# Senslope_Alpha_5_0.net
KiCad netlist of a schematic drawn in EAGLE
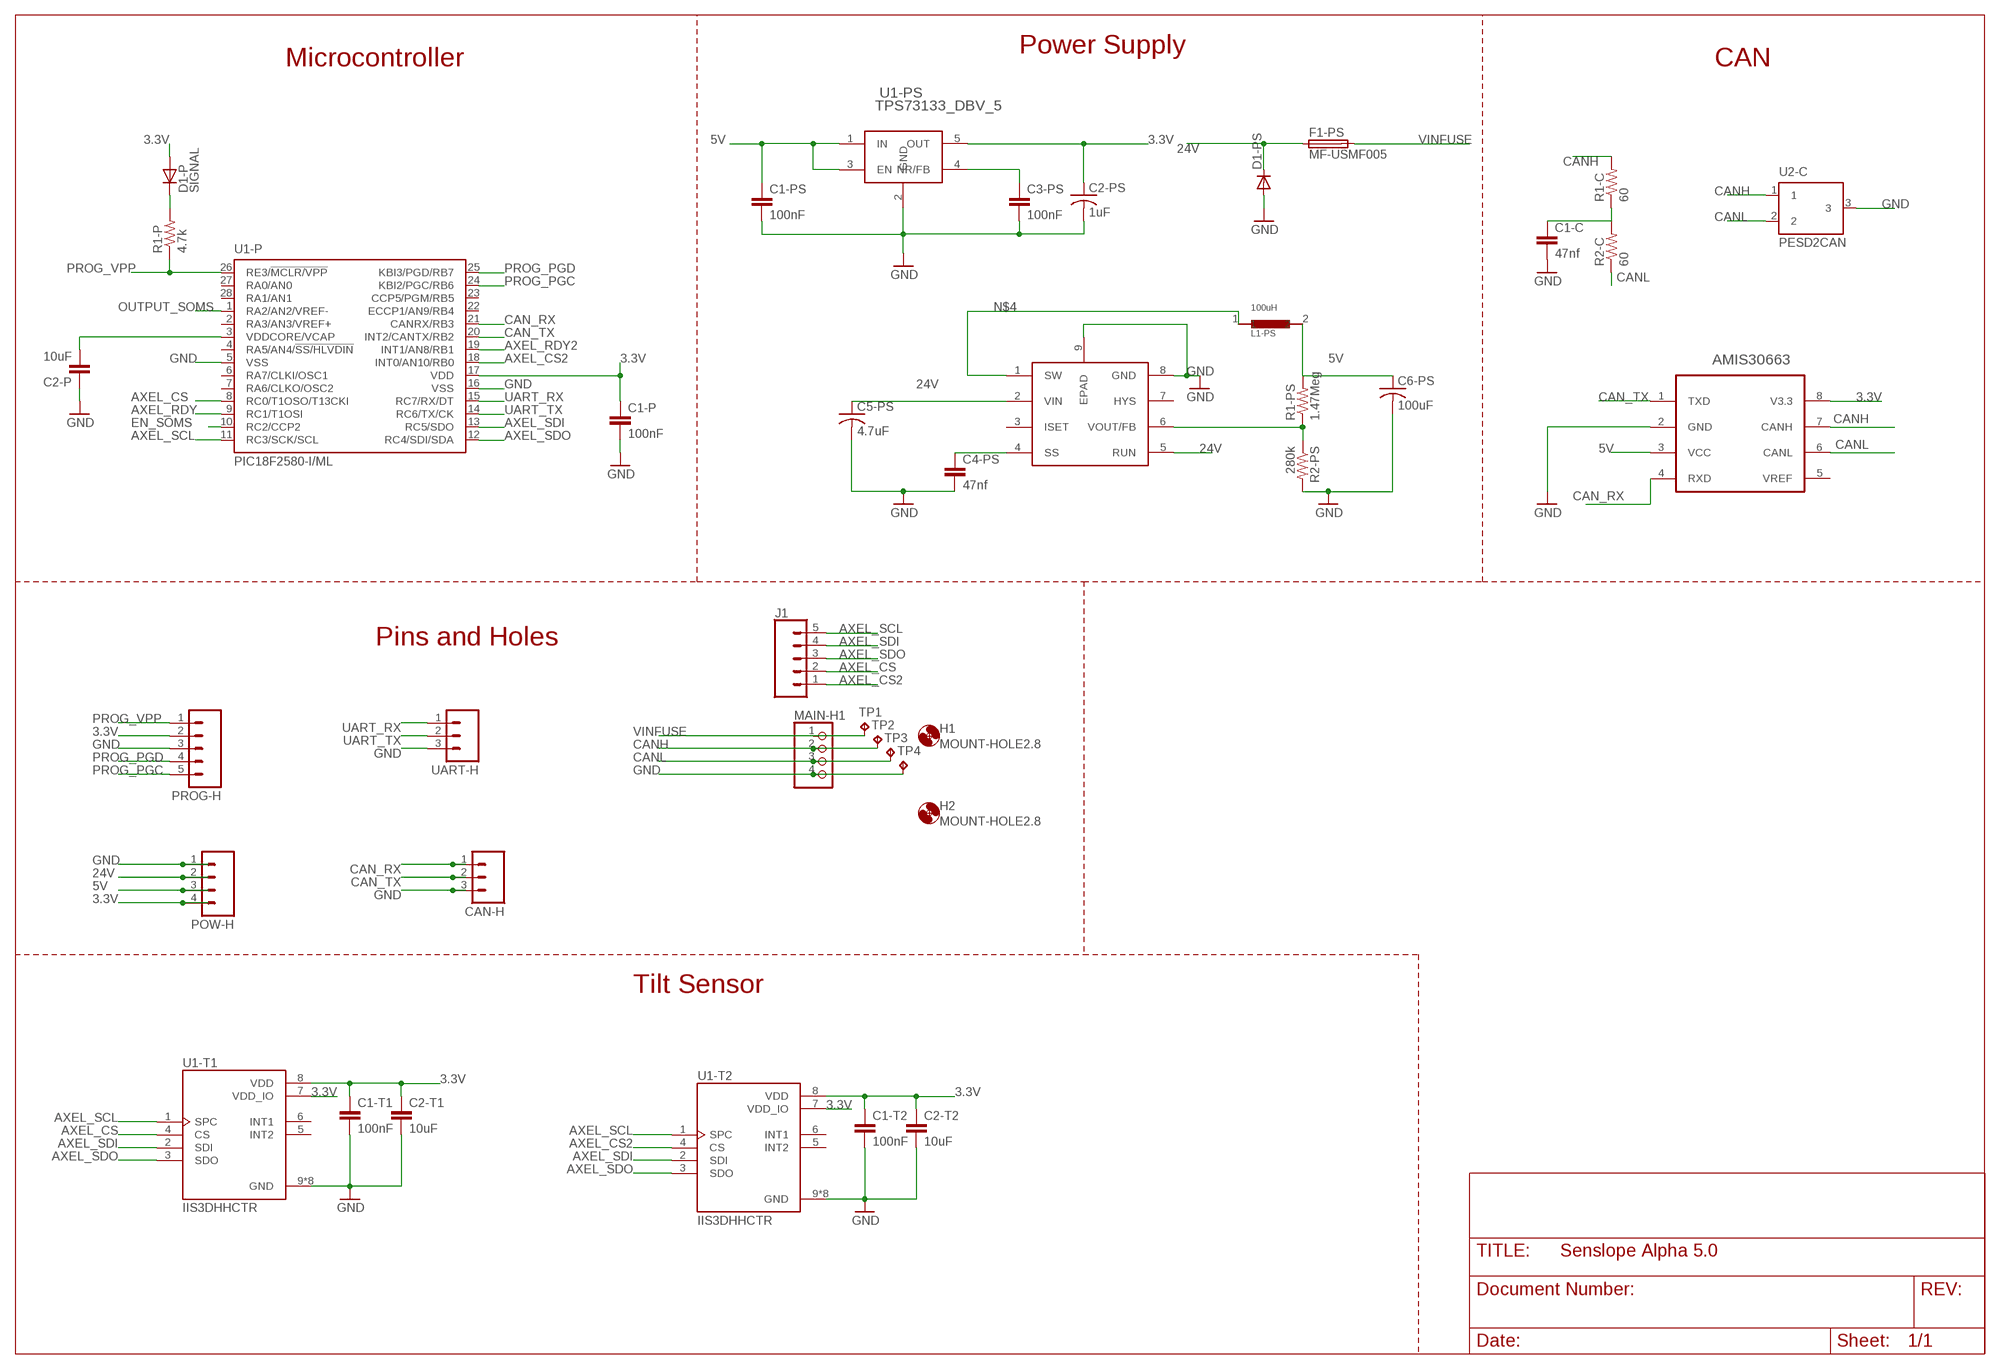
[diagram p0: schematic, sheet 1]

(export (version "E")
  (design (tool "Eeschema 10.0.6"))
  (components
    (comp (ref "C1-C")
      (value "47nf")
      (footprint "eagle-import:C0805")
      (libsource (lib "eagle-import") (part "C-EUC0805"))
    )
    (comp (ref "C1-P")
      (value "100nF")
      (footprint "eagle-import:C0603")
      (libsource (lib "eagle-import") (part "resistor_C-EUC0603"))
    )
    (comp (ref "C1-PS")
      (value "100nF")
      (footprint "eagle-import:C0603")
      (libsource (lib "eagle-import") (part "C-EUC0603"))
    )
    (comp (ref "C1-T1")
      (value "100nF")
      (footprint "eagle-import:C0603")
      (libsource (lib "eagle-import") (part "C-EUC0603"))
    )
    (comp (ref "C1-T2")
      (value "100nF")
      (footprint "eagle-import:C0603")
      (libsource (lib "eagle-import") (part "C-EUC0603"))
    )
    (comp (ref "C2-P")
      (value "10uF")
      (footprint "eagle-import:C0603")
      (libsource (lib "eagle-import") (part "C-EUC0603"))
    )
    (comp (ref "C2-PS")
      (value "1uF")
      (footprint "eagle-import:C0402")
      (libsource (lib "eagle-import") (part "C-USC0402"))
    )
    (comp (ref "C2-T1")
      (value "10uF")
      (footprint "eagle-import:C0603")
      (libsource (lib "eagle-import") (part "C-EUC0603"))
    )
    (comp (ref "C2-T2")
      (value "10uF")
      (footprint "eagle-import:C0603")
      (libsource (lib "eagle-import") (part "C-EUC0603"))
    )
    (comp (ref "C3-PS")
      (value "100nF")
      (footprint "eagle-import:C0603")
      (libsource (lib "eagle-import") (part "C-EUC0603"))
    )
    (comp (ref "C4-PS")
      (value "47nf")
      (footprint "eagle-import:C0805")
      (libsource (lib "eagle-import") (part "C-EUC0805"))
    )
    (comp (ref "C5-PS")
      (value "4.7uF")
      (footprint "eagle-import:C1206K")
      (libsource (lib "eagle-import") (part "C-USC1206K"))
    )
    (comp (ref "C6-PS")
      (value "100uF")
      (footprint "eagle-import:C1210K")
      (libsource (lib "eagle-import") (part "C-USC1210K"))
    )
    (comp (ref "CAN-H")
      (value "UART")
      (footprint "eagle-import:1X03_NO_SILK")
      (libsource (lib "eagle-import") (part "M031X03_NO_SILK"))
    )
    (comp (ref "D1-P")
      (value "SIGNAL")
      (footprint "eagle-import:DIODE-0603")
      (libsource (lib "eagle-import") (part "DIODE0603"))
    )
    (comp (ref "D1-PS")
      (value "DIODE-DO-214AC")
      (footprint "eagle-import:DO-214AC")
      (libsource (lib "eagle-import") (part "DIODE-DO-214AC"))
    )
    (comp (ref "F1-PS")
      (value "MF-USMF005")
      (footprint "eagle-import:1210")
      (libsource (lib "eagle-import") (part "MF-USMF075"))
    )
    (comp (ref "H1")
      (value "MOUNT-HOLE2.8")
      (footprint "eagle-import:2,8")
      (libsource (lib "eagle-import") (part "MOUNT-HOLE2.8"))
    )
    (comp (ref "H2")
      (value "MOUNT-HOLE2.8")
      (footprint "eagle-import:2,8")
      (libsource (lib "eagle-import") (part "MOUNT-HOLE2.8"))
    )
    (comp (ref "J1")
      (value "CONN_05NO_SILK")
      (footprint "eagle-import:1X05_NO_SILK")
      (libsource (lib "eagle-import") (part "CONN_05NO_SILK"))
    )
    (comp (ref "L1-PS")
      (value "100uH")
      (footprint "eagle-import:1210")
      (libsource (lib "eagle-import") (part "LQH32PN101MN0L"))
    )
    (comp (ref "MAIN-H1")
      (value "PINHD-1X04_2.54")
      (footprint "eagle-import:1X04")
      (libsource (lib "eagle-import") (part "PINHD-1X04_2.54"))
    )
    (comp (ref "POW-H")
      (value "M041X04_NO_SILK")
      (footprint "eagle-import:1X04_NO_SILK")
      (libsource (lib "eagle-import") (part "M041X04_NO_SILK"))
    )
    (comp (ref "PROG-H")
      (value "M05PTH")
      (footprint "eagle-import:1X05@1")
      (libsource (lib "eagle-import") (part "M05PTH"))
    )
    (comp (ref "R1-C")
      (value "60")
      (footprint "eagle-import:R0805")
      (libsource (lib "eagle-import") (part "R-US_R0805"))
    )
    (comp (ref "R1-P")
      (value "4.7k")
      (footprint "eagle-import:R0603")
      (libsource (lib "eagle-import") (part "resistor_R-US_R0603"))
    )
    (comp (ref "R1-PS")
      (value "1.47Meg")
      (footprint "eagle-import:R0805")
      (libsource (lib "eagle-import") (part "R-US_R0805"))
    )
    (comp (ref "R2-C")
      (value "60")
      (footprint "eagle-import:R0805")
      (libsource (lib "eagle-import") (part "R-US_R0805"))
    )
    (comp (ref "R2-PS")
      (value "280k")
      (footprint "eagle-import:R0805")
      (libsource (lib "eagle-import") (part "R-US_R0805"))
    )
    (comp (ref "TP1")
      (value "TPTP10SQ")
      (footprint "eagle-import:TP10SQ")
      (libsource (lib "eagle-import") (part "TPTP10SQ"))
    )
    (comp (ref "TP2")
      (value "TPTP10SQ")
      (footprint "eagle-import:TP10SQ")
      (libsource (lib "eagle-import") (part "TPTP10SQ"))
    )
    (comp (ref "TP3")
      (value "TPTP10SQ")
      (footprint "eagle-import:TP10SQ")
      (libsource (lib "eagle-import") (part "TPTP10SQ"))
    )
    (comp (ref "TP4")
      (value "TPTP10SQ")
      (footprint "eagle-import:TP10SQ")
      (libsource (lib "eagle-import") (part "TPTP10SQ"))
    )
    (comp (ref "U1-P")
      (value "PIC18F2580-I/ML")
      (footprint "eagle-import:QFN28-ML_6X6MM")
      (fields (field (name "MF") "MICROCHIP"))
      (libsource (lib "eagle-import") (part "PIC18F280-I/ML5"))
    )
    (comp (ref "U1-PS")
      (value "TPS73133_DBV_5")
      (footprint "eagle-import:DBV5")
      (fields
        (field (name "GENERIC_PART_NUMBER") "TPS73133")
        (field (name "MANUFACTURER") "Texas Instruments")
        (field (name "MANUFACTURER_PART_NUMBER") "tps73133_dbv_5")
      )
      (libsource (lib "eagle-import") (part "TPS73133_DBV_5"))
    )
    (comp (ref "U1-T1")
      (value "IIS3DHHCTR")
      (footprint "eagle-import:IC_IIS3DHHCTR")
      (fields (field (name "MF") "STMicroelectronics"))
      (libsource (lib "eagle-import") (part "IIS3DHHCTR"))
    )
    (comp (ref "U1-T2")
      (value "IIS3DHHCTR")
      (footprint "eagle-import:IC_IIS3DHHCTR")
      (fields (field (name "MF") "STMicroelectronics"))
      (libsource (lib "eagle-import") (part "IIS3DHHCTR"))
    )
    (comp (ref "U2")
      (value "AMIS30663CAN")
      (footprint "eagle-import:SOIC8")
      (fields (field (name "MPN") "AMIS30663"))
      (libsource (lib "eagle-import") (part "AMIS30663CAN"))
    )
    (comp (ref "U2-C")
      (value "PESD2CAN")
      (footprint "eagle-import:SOT23")
      (libsource (lib "eagle-import") (part "PESD2CAN"))
    )
    (comp (ref "U2-PS")
      (value "LTC3631-5")
      (footprint "eagle-import:MSOP8E")
      (libsource (lib "eagle-import") (part "LTC3631"))
    )
    (comp (ref "UART-H")
      (value "UART")
      (footprint "eagle-import:1X03_NO_SILK")
      (libsource (lib "eagle-import") (part "M031X03_NO_SILK"))
    )
  )
  (nets
    (net (code "1") (name "/3.3V") (class "Default")
      (node (ref "C1-P") (pin "1") (pinfunction "1_1") (pintype "passive"))
      (node (ref "C1-T1") (pin "1") (pinfunction "1_1") (pintype "passive"))
      (node (ref "C1-T2") (pin "1") (pinfunction "1_1") (pintype "passive"))
      (node (ref "C2-PS") (pin "1") (pinfunction "1_1") (pintype "passive"))
      (node (ref "C2-T1") (pin "1") (pinfunction "1_1") (pintype "passive"))
      (node (ref "C2-T2") (pin "1") (pinfunction "1_1") (pintype "passive"))
      (node (ref "D1-P") (pin "A") (pinfunction "A_A") (pintype "passive"))
      (node (ref "POW-H") (pin "4") (pinfunction "4_4") (pintype "passive"))
      (node (ref "PROG-H") (pin "2") (pinfunction "2_2") (pintype "passive"))
      (node (ref "U1-P") (pin "17") (pinfunction "VDD_17") (pintype "power_in"))
      (node (ref "U1-PS") (pin "5") (pinfunction "OUT_5") (pintype "output"))
      (node (ref "U1-T1") (pin "7") (pinfunction "VDD_IO_7") (pintype "power_in"))
      (node (ref "U1-T1") (pin "8") (pinfunction "VDD_8") (pintype "power_in"))
      (node (ref "U1-T2") (pin "7") (pinfunction "VDD_IO_7") (pintype "power_in"))
      (node (ref "U1-T2") (pin "8") (pinfunction "VDD_8") (pintype "power_in"))
      (node (ref "U2") (pin "8") (pinfunction "V3.3_8") (pintype "bidirectional"))
    )
    (net (code "2") (name "/5V") (class "Default")
      (node (ref "C1-PS") (pin "1") (pinfunction "1_1") (pintype "passive"))
      (node (ref "C6-PS") (pin "1") (pinfunction "1_1") (pintype "passive"))
      (node (ref "L1-PS") (pin "2") (pinfunction "2_2") (pintype "bidirectional"))
      (node (ref "POW-H") (pin "3") (pinfunction "3_3") (pintype "passive"))
      (node (ref "R1-PS") (pin "2") (pinfunction "2_2") (pintype "passive"))
      (node (ref "U1-PS") (pin "1") (pinfunction "IN_1") (pintype "input"))
      (node (ref "U1-PS") (pin "3") (pinfunction "EN_3") (pintype "passive"))
      (node (ref "U2") (pin "3") (pinfunction "VCC_3") (pintype "bidirectional"))
    )
    (net (code "3") (name "/24V") (class "Default")
      (node (ref "C5-PS") (pin "1") (pinfunction "1_1") (pintype "passive"))
      (node (ref "D1-PS") (pin "1") (pinfunction "C_1") (pintype "passive"))
      (node (ref "F1-PS") (pin "1") (pinfunction "1_1") (pintype "passive"))
      (node (ref "POW-H") (pin "2") (pinfunction "2_2") (pintype "passive"))
      (node (ref "U2-PS") (pin "2") (pinfunction "VIN_2") (pintype "bidirectional"))
      (node (ref "U2-PS") (pin "5") (pinfunction "RUN_5") (pintype "bidirectional"))
    )
    (net (code "4") (name "/AXEL_CS") (class "Default")
      (node (ref "J1") (pin "2") (pinfunction "2_2") (pintype "passive"))
      (node (ref "U1-P") (pin "8") (pinfunction "RC0/T1OSO/T13CKI_8") (pintype "bidirectional"))
      (node (ref "U1-T1") (pin "4") (pinfunction "CS_4") (pintype "input"))
    )
    (net (code "5") (name "/AXEL_CS2") (class "Default")
      (node (ref "J1") (pin "1") (pinfunction "1_1") (pintype "passive"))
      (node (ref "U1-P") (pin "18") (pinfunction "INT0/AN10/RB0_18") (pintype "bidirectional"))
      (node (ref "U1-T2") (pin "4") (pinfunction "CS_4") (pintype "input"))
    )
    (net (code "6") (name "/AXEL_RDY") (class "Default")
      (node (ref "U1-P") (pin "9") (pinfunction "RC1/T1OSI_9") (pintype "bidirectional"))
    )
    (net (code "7") (name "/AXEL_RDY2") (class "Default")
      (node (ref "U1-P") (pin "19") (pinfunction "INT1/AN8/RB1_19") (pintype "bidirectional"))
    )
    (net (code "8") (name "/AXEL_SCL") (class "Default")
      (node (ref "J1") (pin "5") (pinfunction "5_5") (pintype "passive"))
      (node (ref "U1-P") (pin "11") (pinfunction "RC3/SCK/SCL_11") (pintype "bidirectional"))
      (node (ref "U1-T1") (pin "1") (pinfunction "SPC_1") (pintype "input"))
      (node (ref "U1-T2") (pin "1") (pinfunction "SPC_1") (pintype "input"))
    )
    (net (code "9") (name "/AXEL_SDI") (class "Default")
      (node (ref "J1") (pin "4") (pinfunction "4_4") (pintype "passive"))
      (node (ref "U1-P") (pin "13") (pinfunction "RC5/SDO_13") (pintype "bidirectional"))
      (node (ref "U1-T1") (pin "2") (pinfunction "SDI_2") (pintype "input"))
      (node (ref "U1-T2") (pin "2") (pinfunction "SDI_2") (pintype "input"))
    )
    (net (code "10") (name "/AXEL_SDO") (class "Default")
      (node (ref "J1") (pin "3") (pinfunction "3_3") (pintype "passive"))
      (node (ref "U1-P") (pin "12") (pinfunction "RC4/SDI/SDA_12") (pintype "bidirectional"))
      (node (ref "U1-T1") (pin "3") (pinfunction "SDO_3") (pintype "output"))
      (node (ref "U1-T2") (pin "3") (pinfunction "SDO_3") (pintype "output"))
    )
    (net (code "11") (name "/CANH") (class "Default")
      (node (ref "MAIN-H1") (pin "2") (pinfunction "2_2") (pintype "passive"))
      (node (ref "R1-C") (pin "2") (pinfunction "2_2") (pintype "passive"))
      (node (ref "TP2") (pin "TP") (pinfunction "TP_TP") (pintype "input"))
      (node (ref "U2") (pin "7") (pinfunction "CANH_7") (pintype "bidirectional"))
      (node (ref "U2-C") (pin "1") (pinfunction "1_1") (pintype "input"))
    )
    (net (code "12") (name "/CANL") (class "Default")
      (node (ref "MAIN-H1") (pin "3") (pinfunction "3_3") (pintype "passive"))
      (node (ref "R2-C") (pin "1") (pinfunction "1_1") (pintype "passive"))
      (node (ref "TP3") (pin "TP") (pinfunction "TP_TP") (pintype "input"))
      (node (ref "U2") (pin "6") (pinfunction "CANL_6") (pintype "bidirectional"))
      (node (ref "U2-C") (pin "2") (pinfunction "2_2") (pintype "power_in"))
    )
    (net (code "13") (name "/CAN_RX") (class "Default")
      (node (ref "CAN-H") (pin "1") (pinfunction "1_1") (pintype "passive"))
      (node (ref "U1-P") (pin "21") (pinfunction "CANRX/RB3_21") (pintype "bidirectional"))
      (node (ref "U2") (pin "4") (pinfunction "RXD_4") (pintype "bidirectional"))
    )
    (net (code "14") (name "/CAN_TX") (class "Default")
      (node (ref "CAN-H") (pin "2") (pinfunction "2_2") (pintype "passive"))
      (node (ref "U1-P") (pin "20") (pinfunction "INT2/CANTX/RB2_20") (pintype "bidirectional"))
      (node (ref "U2") (pin "1") (pinfunction "TXD_1") (pintype "bidirectional"))
    )
    (net (code "15") (name "/EN_SOMS") (class "Default")
      (node (ref "U1-P") (pin "10") (pinfunction "RC2/CCP2_10") (pintype "bidirectional"))
    )
    (net (code "16") (name "/N$4") (class "Default")
      (node (ref "L1-PS") (pin "1") (pinfunction "1_1") (pintype "bidirectional"))
      (node (ref "U2-PS") (pin "1") (pinfunction "SW_1") (pintype "bidirectional"))
    )
    (net (code "17") (name "/OUTPUT_SOMS") (class "Default")
      (node (ref "U1-P") (pin "1") (pinfunction "RA2/AN2/VREF-_1") (pintype "bidirectional"))
    )
    (net (code "18") (name "/PROG_PGC") (class "Default")
      (node (ref "PROG-H") (pin "5") (pinfunction "5_5") (pintype "passive"))
      (node (ref "U1-P") (pin "24") (pinfunction "KBI2/PGC/RB6_24") (pintype "bidirectional"))
    )
    (net (code "19") (name "/PROG_PGD") (class "Default")
      (node (ref "PROG-H") (pin "4") (pinfunction "4_4") (pintype "passive"))
      (node (ref "U1-P") (pin "25") (pinfunction "KBI3/PGD/RB7_25") (pintype "bidirectional"))
    )
    (net (code "20") (name "/PROG_VPP") (class "Default")
      (node (ref "PROG-H") (pin "1") (pinfunction "1_1") (pintype "passive"))
      (node (ref "R1-P") (pin "1") (pinfunction "1_1") (pintype "passive"))
      (node (ref "U1-P") (pin "26") (pinfunction "RE3/~{MCLR/VPP}_26") (pintype "input"))
    )
    (net (code "21") (name "/UART_RX") (class "Default")
      (node (ref "U1-P") (pin "15") (pinfunction "RC7/RX/DT_15") (pintype "bidirectional"))
      (node (ref "UART-H") (pin "1") (pinfunction "1_1") (pintype "passive"))
    )
    (net (code "22") (name "/UART_TX") (class "Default")
      (node (ref "U1-P") (pin "14") (pinfunction "RC6/TX/CK_14") (pintype "bidirectional"))
      (node (ref "UART-H") (pin "2") (pinfunction "2_2") (pintype "passive"))
    )
    (net (code "23") (name "/VINFUSE") (class "Default")
      (node (ref "F1-PS") (pin "2") (pinfunction "2_2") (pintype "passive"))
      (node (ref "MAIN-H1") (pin "1") (pinfunction "1_1") (pintype "passive"))
      (node (ref "TP1") (pin "TP") (pinfunction "TP_TP") (pintype "input"))
    )
    (net (code "24") (name "GND") (class "Default")
      (node (ref "C1-C") (pin "2") (pinfunction "2_2") (pintype "passive"))
      (node (ref "C1-P") (pin "2") (pinfunction "2_2") (pintype "passive"))
      (node (ref "C1-PS") (pin "2") (pinfunction "2_2") (pintype "passive"))
      (node (ref "C1-T1") (pin "2") (pinfunction "2_2") (pintype "passive"))
      (node (ref "C1-T2") (pin "2") (pinfunction "2_2") (pintype "passive"))
      (node (ref "C2-P") (pin "1") (pinfunction "1_1") (pintype "passive"))
      (node (ref "C2-PS") (pin "2") (pinfunction "2_2") (pintype "passive"))
      (node (ref "C2-T1") (pin "2") (pinfunction "2_2") (pintype "passive"))
      (node (ref "C2-T2") (pin "2") (pinfunction "2_2") (pintype "passive"))
      (node (ref "C3-PS") (pin "2") (pinfunction "2_2") (pintype "passive"))
      (node (ref "C4-PS") (pin "2") (pinfunction "2_2") (pintype "passive"))
      (node (ref "C5-PS") (pin "2") (pinfunction "2_2") (pintype "passive"))
      (node (ref "C6-PS") (pin "2") (pinfunction "2_2") (pintype "passive"))
      (node (ref "CAN-H") (pin "3") (pinfunction "3_3") (pintype "passive"))
      (node (ref "D1-PS") (pin "2") (pinfunction "A_2") (pintype "passive"))
      (node (ref "MAIN-H1") (pin "4") (pinfunction "4_4") (pintype "passive"))
      (node (ref "POW-H") (pin "1") (pinfunction "1_1") (pintype "passive"))
      (node (ref "PROG-H") (pin "3") (pinfunction "3_3") (pintype "passive"))
      (node (ref "R2-PS") (pin "2") (pinfunction "2_2") (pintype "passive"))
      (node (ref "TP4") (pin "TP") (pinfunction "TP_TP") (pintype "input"))
      (node (ref "U1-P") (pin "16") (pinfunction "VSS_16") (pintype "power_in"))
      (node (ref "U1-P") (pin "5") (pinfunction "VSS_5") (pintype "power_in"))
      (node (ref "U1-PS") (pin "2") (pinfunction "GND_2") (pintype "power_in"))
      (node (ref "U1-T1") (pin "10") (pinfunction "GND_10") (pintype "power_in"))
      (node (ref "U1-T1") (pin "11") (pinfunction "GND_11") (pintype "power_in"))
      (node (ref "U1-T1") (pin "12") (pinfunction "GND_12") (pintype "power_in"))
      (node (ref "U1-T1") (pin "13") (pinfunction "GND_13") (pintype "power_in"))
      (node (ref "U1-T1") (pin "14") (pinfunction "GND_14") (pintype "power_in"))
      (node (ref "U1-T1") (pin "15") (pinfunction "GND_15") (pintype "power_in"))
      (node (ref "U1-T1") (pin "16") (pinfunction "GND_16") (pintype "power_in"))
      (node (ref "U1-T1") (pin "9") (pinfunction "GND_9") (pintype "power_in"))
      (node (ref "U1-T2") (pin "10") (pinfunction "GND_10") (pintype "power_in"))
      (node (ref "U1-T2") (pin "11") (pinfunction "GND_11") (pintype "power_in"))
      (node (ref "U1-T2") (pin "12") (pinfunction "GND_12") (pintype "power_in"))
      (node (ref "U1-T2") (pin "13") (pinfunction "GND_13") (pintype "power_in"))
      (node (ref "U1-T2") (pin "14") (pinfunction "GND_14") (pintype "power_in"))
      (node (ref "U1-T2") (pin "15") (pinfunction "GND_15") (pintype "power_in"))
      (node (ref "U1-T2") (pin "16") (pinfunction "GND_16") (pintype "power_in"))
      (node (ref "U1-T2") (pin "9") (pinfunction "GND_9") (pintype "power_in"))
      (node (ref "U2") (pin "2") (pinfunction "GND_2") (pintype "bidirectional"))
      (node (ref "U2-C") (pin "3") (pinfunction "3_3") (pintype "output"))
      (node (ref "U2-PS") (pin "8") (pinfunction "GND_8") (pintype "bidirectional"))
      (node (ref "U2-PS") (pin "9") (pinfunction "EPAD_9") (pintype "bidirectional"))
      (node (ref "UART-H") (pin "3") (pinfunction "3_3") (pintype "passive"))
    )
    (net (code "25") (name "Net-(C1-C-Pad1)") (class "Default")
      (node (ref "C1-C") (pin "1") (pinfunction "1_1") (pintype "passive"))
      (node (ref "R1-C") (pin "1") (pinfunction "1_1") (pintype "passive"))
      (node (ref "R2-C") (pin "2") (pinfunction "2_2") (pintype "passive"))
    )
    (net (code "26") (name "Net-(D1-P-PadC)") (class "Default")
      (node (ref "D1-P") (pin "C") (pinfunction "C_C") (pintype "passive"))
      (node (ref "R1-P") (pin "2") (pinfunction "2_2") (pintype "passive"))
    )
    (net (code "27") (name "Net-(U1-P-VDDCORE{slash}VCAP)") (class "Default")
      (node (ref "C2-P") (pin "2") (pinfunction "2_2") (pintype "passive"))
      (node (ref "U1-P") (pin "3") (pinfunction "VDDCORE/VCAP_3") (pintype "bidirectional"))
    )
    (net (code "28") (name "Net-(U1-PS-NR{slash}FB)") (class "Default")
      (node (ref "C3-PS") (pin "1") (pinfunction "1_1") (pintype "passive"))
      (node (ref "U1-PS") (pin "4") (pinfunction "NR/FB_4") (pintype "passive"))
    )
    (net (code "29") (name "Net-(U2-PS-SS)") (class "Default")
      (node (ref "C4-PS") (pin "1") (pinfunction "1_1") (pintype "passive"))
      (node (ref "U2-PS") (pin "4") (pinfunction "SS_4") (pintype "bidirectional"))
    )
    (net (code "30") (name "Net-(U2-PS-VOUT{slash}FB)") (class "Default")
      (node (ref "R1-PS") (pin "1") (pinfunction "1_1") (pintype "passive"))
      (node (ref "R2-PS") (pin "1") (pinfunction "1_1") (pintype "passive"))
      (node (ref "U2-PS") (pin "6") (pinfunction "VOUT/FB_6") (pintype "bidirectional"))
    )
    (net (code "31") (name "unconnected-(U1-P-CCP5{slash}PGM{slash}RB5-Pad23)") (class "Default")
      (node (ref "U1-P") (pin "23") (pinfunction "CCP5/PGM/RB5_23") (pintype "bidirectional"))
    )
    (net (code "32") (name "unconnected-(U1-P-ECCP1{slash}AN9{slash}RB4-Pad22)") (class "Default")
      (node (ref "U1-P") (pin "22") (pinfunction "ECCP1/AN9/RB4_22") (pintype "bidirectional"))
    )
    (net (code "33") (name "unconnected-(U1-P-RA0{slash}AN0-Pad27)") (class "Default")
      (node (ref "U1-P") (pin "27") (pinfunction "RA0/AN0_27") (pintype "bidirectional"))
    )
    (net (code "34") (name "unconnected-(U1-P-RA1{slash}AN1-Pad28)") (class "Default")
      (node (ref "U1-P") (pin "28") (pinfunction "RA1/AN1_28") (pintype "bidirectional"))
    )
    (net (code "35") (name "unconnected-(U1-P-RA3{slash}AN3{slash}VREF+-Pad2)") (class "Default")
      (node (ref "U1-P") (pin "2") (pinfunction "RA3/AN3/VREF+_2") (pintype "bidirectional"))
    )
    (net (code "36") (name "unconnected-(U1-P-RA5{slash}AN4{slash}~{SS{slash}HLVDIN}-Pad4)") (class "Default")
      (node (ref "U1-P") (pin "4") (pinfunction "RA5/AN4/~{SS/HLVDIN}_4") (pintype "bidirectional"))
    )
    (net (code "37") (name "unconnected-(U1-P-RA6{slash}CLKO{slash}OSC2-Pad7)") (class "Default")
      (node (ref "U1-P") (pin "7") (pinfunction "RA6/CLKO/OSC2_7") (pintype "output"))
    )
    (net (code "38") (name "unconnected-(U1-P-RA7{slash}CLKI{slash}OSC1-Pad6)") (class "Default")
      (node (ref "U1-P") (pin "6") (pinfunction "RA7/CLKI/OSC1_6") (pintype "input"))
    )
    (net (code "39") (name "unconnected-(U1-T1-INT1-Pad6)") (class "Default")
      (node (ref "U1-T1") (pin "6") (pinfunction "INT1_6") (pintype "output"))
    )
    (net (code "40") (name "unconnected-(U1-T1-INT2-Pad5)") (class "Default")
      (node (ref "U1-T1") (pin "5") (pinfunction "INT2_5") (pintype "output"))
    )
    (net (code "41") (name "unconnected-(U1-T2-INT1-Pad6)") (class "Default")
      (node (ref "U1-T2") (pin "6") (pinfunction "INT1_6") (pintype "output"))
    )
    (net (code "42") (name "unconnected-(U1-T2-INT2-Pad5)") (class "Default")
      (node (ref "U1-T2") (pin "5") (pinfunction "INT2_5") (pintype "output"))
    )
    (net (code "43") (name "unconnected-(U2-PS-HYS-Pad7)") (class "Default")
      (node (ref "U2-PS") (pin "7") (pinfunction "HYS_7") (pintype "bidirectional"))
    )
    (net (code "44") (name "unconnected-(U2-PS-ISET-Pad3)") (class "Default")
      (node (ref "U2-PS") (pin "3") (pinfunction "ISET_3") (pintype "bidirectional"))
    )
    (net (code "45") (name "unconnected-(U2-VREF-Pad5)") (class "Default")
      (node (ref "U2") (pin "5") (pinfunction "VREF_5") (pintype "bidirectional"))
    )
  )
)
